# Com_Uart.net
KiCad netlist of a schematic drawn in Altium Designer
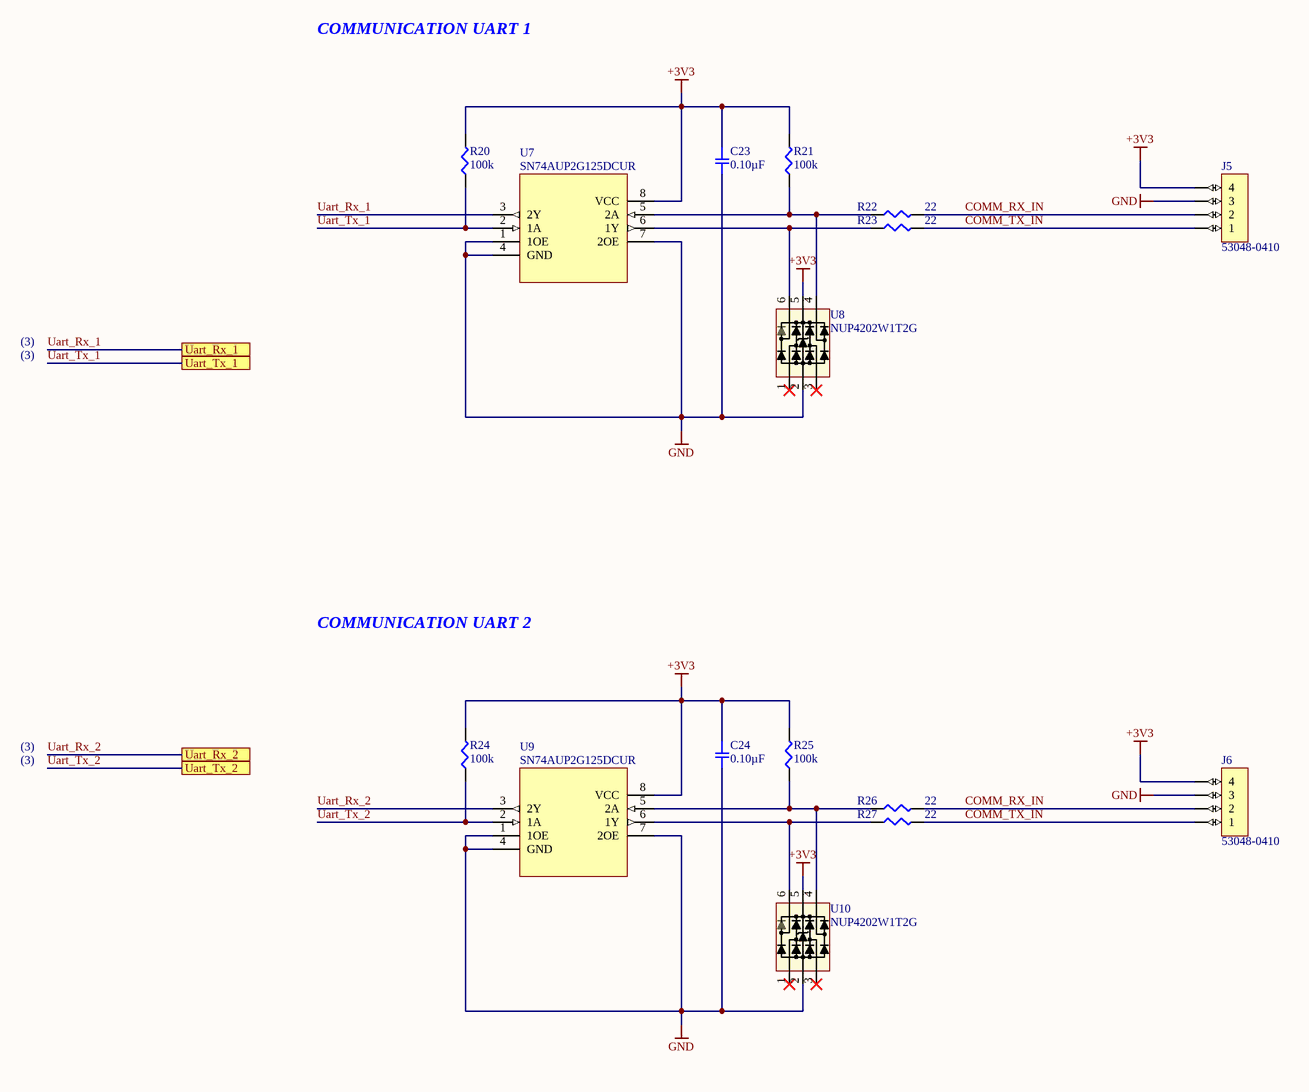
[diagram p0: Com_Uart.SchDoc]

(export (version "E")
  (design (tool "Eeschema 10.0.6"))
  (components
    (comp (ref "C23")
      (value "0.10µF")
      (footprint "SMD-0603C")
      (description "CAP CER 0.1UF 50V X7R 0603")
      (fields
        (field (name "DIGI-KEY PART NUMBER") "490-5798-1-ND")
        (field (name "MANUFACTURER") "Murata Electronics North America")
      )
      (libsource (lib "capacitor_murata_0603") (part "GCJ188R71H104KA12D"))
    )
    (comp (ref "C24")
      (value "0.10µF")
      (footprint "SMD-0603C")
      (description "CAP CER 0.1UF 50V X7R 0603")
      (fields
        (field (name "DIGI-KEY PART NUMBER") "490-5798-1-ND")
        (field (name "MANUFACTURER") "Murata Electronics North America")
      )
      (libsource (lib "capacitor_murata_0603") (part "GCJ188R71H104KA12D"))
    )
    (comp (ref "J5")
      (value "53048-0410")
      (footprint "CONN_4_POS__0530480410")
      (description "CONN HEADER R/A 4POS 1.25MM")
      (fields (field (name "MANUFACTURER") "Molex"))
      (libsource (lib "Altium_Lib") (part "CONN_4_POS__0530480410"))
    )
    (comp (ref "J6")
      (value "53048-0410")
      (footprint "CONN_4_POS__0530480410")
      (description "CONN HEADER R/A 4POS 1.25MM")
      (fields (field (name "MANUFACTURER") "Molex"))
      (libsource (lib "Altium_Lib") (part "CONN_4_POS__0530480410"))
    )
    (comp (ref "R20")
      (value "100k")
      (footprint "SMD-0603-RES")
      (description "RES SMD 100K OHM 1% 1/10W 0603")
      (fields
        (field (name "PART NUMBER") "ERJ-3EKF1003V")
        (field (name "DIGI-KEY PART NUMBER") "P100KHCT-ND")
      )
      (libsource (lib "Panasonic_ERJ_0603") (part "ERJ-3EKF1003V"))
    )
    (comp (ref "R21")
      (value "100k")
      (footprint "SMD-0603-RES")
      (description "RES SMD 100K OHM 1% 1/10W 0603")
      (fields
        (field (name "PART NUMBER") "ERJ-3EKF1003V")
        (field (name "DIGI-KEY PART NUMBER") "P100KHCT-ND")
      )
      (libsource (lib "Panasonic_ERJ_0603") (part "ERJ-3EKF1003V"))
    )
    (comp (ref "R22")
      (value "22")
      (footprint "SMD-0603-RES")
      (description "RES SMD 22 OHM 1% 1/10W 0603")
      (fields
        (field (name "PART NUMBER") "ERJ-3EKF22R0V")
        (field (name "DIGI-KEY PART NUMBER") "P22.0HCT-ND")
      )
      (libsource (lib "Panasonic_ERJ_0603") (part "ERJ-3EKF22R0V"))
    )
    (comp (ref "R23")
      (value "22")
      (footprint "SMD-0603-RES")
      (description "RES SMD 22 OHM 1% 1/10W 0603")
      (fields
        (field (name "PART NUMBER") "ERJ-3EKF22R0V")
        (field (name "DIGI-KEY PART NUMBER") "P22.0HCT-ND")
      )
      (libsource (lib "Panasonic_ERJ_0603") (part "ERJ-3EKF22R0V"))
    )
    (comp (ref "R24")
      (value "100k")
      (footprint "SMD-0603-RES")
      (description "RES SMD 100K OHM 1% 1/10W 0603")
      (fields
        (field (name "PART NUMBER") "ERJ-3EKF1003V")
        (field (name "DIGI-KEY PART NUMBER") "P100KHCT-ND")
      )
      (libsource (lib "Panasonic_ERJ_0603") (part "ERJ-3EKF1003V"))
    )
    (comp (ref "R25")
      (value "100k")
      (footprint "SMD-0603-RES")
      (description "RES SMD 100K OHM 1% 1/10W 0603")
      (fields
        (field (name "PART NUMBER") "ERJ-3EKF1003V")
        (field (name "DIGI-KEY PART NUMBER") "P100KHCT-ND")
      )
      (libsource (lib "Panasonic_ERJ_0603") (part "ERJ-3EKF1003V"))
    )
    (comp (ref "R26")
      (value "22")
      (footprint "SMD-0603-RES")
      (description "RES SMD 22 OHM 1% 1/10W 0603")
      (fields
        (field (name "PART NUMBER") "ERJ-3EKF22R0V")
        (field (name "DIGI-KEY PART NUMBER") "P22.0HCT-ND")
      )
      (libsource (lib "Panasonic_ERJ_0603") (part "ERJ-3EKF22R0V"))
    )
    (comp (ref "R27")
      (value "22")
      (footprint "SMD-0603-RES")
      (description "RES SMD 22 OHM 1% 1/10W 0603")
      (fields
        (field (name "PART NUMBER") "ERJ-3EKF22R0V")
        (field (name "DIGI-KEY PART NUMBER") "P22.0HCT-ND")
      )
      (libsource (lib "Panasonic_ERJ_0603") (part "ERJ-3EKF22R0V"))
    )
    (comp (ref "U7")
      (value "SN74AUP2G125DCUR")
      (footprint "VFSOP_8")
      (description "Low-Power Dual Bus Buffer Gate With 3-State Outputs 8-VSSOP -40 to 85")
      (fields (field (name "MANUFACTURER") "Texas Instruments"))
      (libsource (lib "Altium_Lib") (part "SN74AUP2G125DCUR"))
    )
    (comp (ref "U8")
      (value "NUP4202W1T2G")
      (footprint "SOT-363")
      (description "TVS DIODE 5VWM 14.5VC SOT363")
      (fields (field (name "MANUFACTURER") "ON Semiconductor"))
      (libsource (lib "Altium_Lib") (part "NUP4202W1T2G"))
    )
    (comp (ref "U9")
      (value "SN74AUP2G125DCUR")
      (footprint "VFSOP_8")
      (description "Low-Power Dual Bus Buffer Gate With 3-State Outputs 8-VSSOP -40 to 85")
      (fields (field (name "MANUFACTURER") "Texas Instruments"))
      (libsource (lib "Altium_Lib") (part "SN74AUP2G125DCUR"))
    )
    (comp (ref "U10")
      (value "NUP4202W1T2G")
      (footprint "SOT-363")
      (description "TVS DIODE 5VWM 14.5VC SOT363")
      (fields (field (name "MANUFACTURER") "ON Semiconductor"))
      (libsource (lib "Altium_Lib") (part "NUP4202W1T2G"))
    )
  )
  (nets
    (net (code "1") (name "+3V3") (class "Default")
      (node (ref "C23") (pin "1") (pinfunction "1_1") (pintype "passive"))
      (node (ref "C24") (pin "1") (pinfunction "1_1") (pintype "passive"))
      (node (ref "J5") (pin "4") (pinfunction "4_4") (pintype "bidirectional"))
      (node (ref "J6") (pin "4") (pinfunction "4_4") (pintype "bidirectional"))
      (node (ref "R20") (pin "2") (pinfunction "2_2") (pintype "passive"))
      (node (ref "R21") (pin "2") (pinfunction "2_2") (pintype "passive"))
      (node (ref "R24") (pin "2") (pinfunction "2_2") (pintype "passive"))
      (node (ref "R25") (pin "2") (pinfunction "2_2") (pintype "passive"))
      (node (ref "U10") (pin "5") (pinfunction "5_5") (pintype "passive"))
      (node (ref "U7") (pin "8") (pinfunction "VCC_8") (pintype "passive"))
      (node (ref "U8") (pin "5") (pinfunction "5_5") (pintype "passive"))
      (node (ref "U9") (pin "8") (pinfunction "VCC_8") (pintype "passive"))
    )
    (net (code "2") (name "/COMM_RX_IN") (class "Default")
      (node (ref "J5") (pin "2") (pinfunction "2_2") (pintype "bidirectional"))
      (node (ref "J6") (pin "2") (pinfunction "2_2") (pintype "bidirectional"))
      (node (ref "R22") (pin "2") (pinfunction "2_2") (pintype "passive"))
      (node (ref "R26") (pin "2") (pinfunction "2_2") (pintype "passive"))
    )
    (net (code "3") (name "/COMM_TX_IN") (class "Default")
      (node (ref "J5") (pin "1") (pinfunction "1_1") (pintype "bidirectional"))
      (node (ref "J6") (pin "1") (pinfunction "1_1") (pintype "bidirectional"))
      (node (ref "R23") (pin "2") (pinfunction "2_2") (pintype "passive"))
      (node (ref "R27") (pin "2") (pinfunction "2_2") (pintype "passive"))
    )
    (net (code "4") (name "/Uart_Rx_1") (class "Default")
      (node (ref "U7") (pin "3") (pinfunction "2Y_3") (pintype "output"))
    )
    (net (code "5") (name "/Uart_Rx_2") (class "Default")
      (node (ref "U9") (pin "3") (pinfunction "2Y_3") (pintype "output"))
    )
    (net (code "6") (name "/Uart_Tx_1") (class "Default")
      (node (ref "R20") (pin "1") (pinfunction "1_1") (pintype "passive"))
      (node (ref "U7") (pin "2") (pinfunction "1A_2") (pintype "input"))
    )
    (net (code "7") (name "/Uart_Tx_2") (class "Default")
      (node (ref "R24") (pin "1") (pinfunction "1_1") (pintype "passive"))
      (node (ref "U9") (pin "2") (pinfunction "1A_2") (pintype "input"))
    )
    (net (code "8") (name "GND") (class "Default")
      (node (ref "C23") (pin "2") (pinfunction "2_2") (pintype "passive"))
      (node (ref "C24") (pin "2") (pinfunction "2_2") (pintype "passive"))
      (node (ref "J5") (pin "3") (pinfunction "3_3") (pintype "bidirectional"))
      (node (ref "J6") (pin "3") (pinfunction "3_3") (pintype "bidirectional"))
      (node (ref "U10") (pin "2") (pinfunction "2_2") (pintype "passive"))
      (node (ref "U7") (pin "1") (pinfunction "1OE_1") (pintype "passive"))
      (node (ref "U7") (pin "4") (pinfunction "GND_4") (pintype "passive"))
      (node (ref "U7") (pin "7") (pinfunction "2OE_7") (pintype "passive"))
      (node (ref "U8") (pin "2") (pinfunction "2_2") (pintype "passive"))
      (node (ref "U9") (pin "1") (pinfunction "1OE_1") (pintype "passive"))
      (node (ref "U9") (pin "4") (pinfunction "GND_4") (pintype "passive"))
      (node (ref "U9") (pin "7") (pinfunction "2OE_7") (pintype "passive"))
    )
    (net (code "9") (name "Net-(U7-1Y)") (class "Default")
      (node (ref "R23") (pin "1") (pinfunction "1_1") (pintype "passive"))
      (node (ref "U7") (pin "6") (pinfunction "1Y_6") (pintype "output"))
      (node (ref "U8") (pin "6") (pinfunction "6_6") (pintype "passive"))
    )
    (net (code "10") (name "Net-(U7-2A)") (class "Default")
      (node (ref "R21") (pin "1") (pinfunction "1_1") (pintype "passive"))
      (node (ref "R22") (pin "1") (pinfunction "1_1") (pintype "passive"))
      (node (ref "U7") (pin "5") (pinfunction "2A_5") (pintype "input"))
      (node (ref "U8") (pin "4") (pinfunction "4_4") (pintype "passive"))
    )
    (net (code "11") (name "Net-(U9-1Y)") (class "Default")
      (node (ref "R27") (pin "1") (pinfunction "1_1") (pintype "passive"))
      (node (ref "U10") (pin "6") (pinfunction "6_6") (pintype "passive"))
      (node (ref "U9") (pin "6") (pinfunction "1Y_6") (pintype "output"))
    )
    (net (code "12") (name "Net-(U9-2A)") (class "Default")
      (node (ref "R25") (pin "1") (pinfunction "1_1") (pintype "passive"))
      (node (ref "R26") (pin "1") (pinfunction "1_1") (pintype "passive"))
      (node (ref "U10") (pin "4") (pinfunction "4_4") (pintype "passive"))
      (node (ref "U9") (pin "5") (pinfunction "2A_5") (pintype "input"))
    )
    (net (code "13") (name "unconnected-(U8-Pad1)") (class "Default")
      (node (ref "U8") (pin "1") (pinfunction "1_1") (pintype "passive+no_connect"))
    )
    (net (code "14") (name "unconnected-(U8-Pad3)") (class "Default")
      (node (ref "U8") (pin "3") (pinfunction "3_3") (pintype "passive+no_connect"))
    )
    (net (code "15") (name "unconnected-(U10-Pad1)") (class "Default")
      (node (ref "U10") (pin "1") (pinfunction "1_1") (pintype "passive+no_connect"))
    )
    (net (code "16") (name "unconnected-(U10-Pad3)") (class "Default")
      (node (ref "U10") (pin "3") (pinfunction "3_3") (pintype "passive+no_connect"))
    )
  )
)
